# apboard.net
KiCad netlist of a schematic drawn in Altium Designer
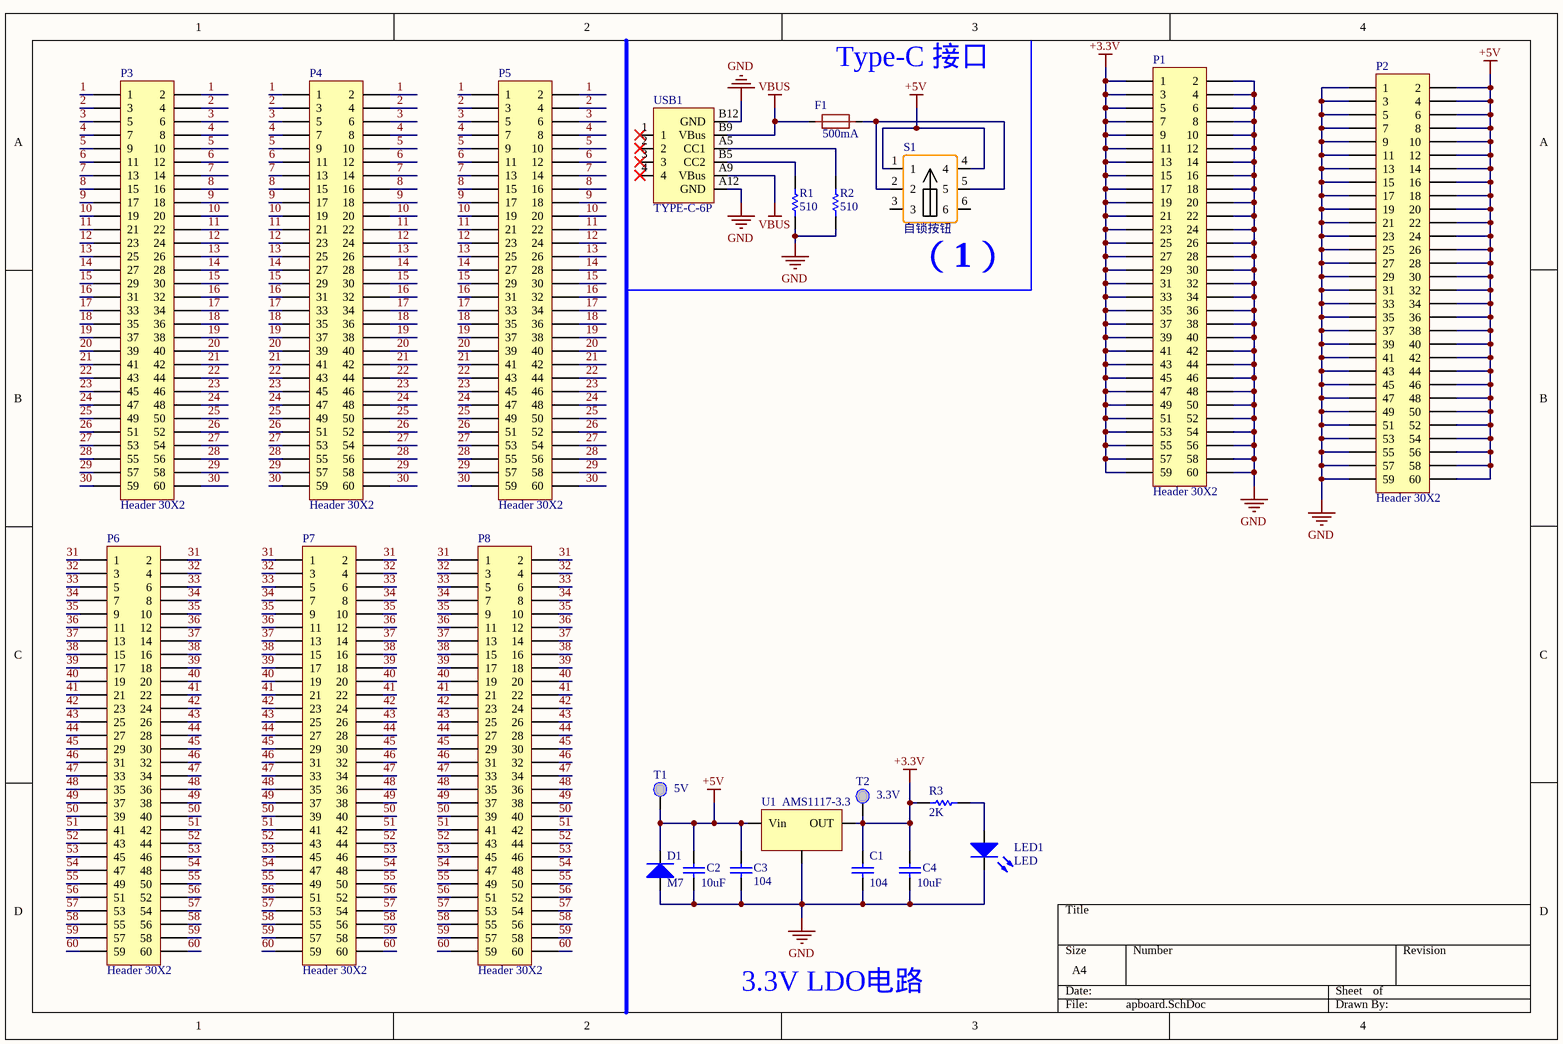
[diagram p0: apboard.SchDoc]

(export (version "E")
  (design (tool "Eeschema 10.0.6"))
  (components
    (comp (ref "C1")
      (value "104")
      (footprint "C0603")
      (description "无极性电容")
      (fields (field (name "Comment") "Cap") (field (name "PUBLISHER") "信念D力量"))
      (libsource (lib "ZSF-90") (part "Cap"))
    )
    (comp (ref "C2")
      (value "10uF")
      (footprint "C1210")
      (description "无极性电容")
      (fields (field (name "Comment") "Cap") (field (name "PUBLISHER") "信念D力量"))
      (libsource (lib "ZSF-90") (part "Cap"))
    )
    (comp (ref "C3")
      (value "104")
      (footprint "C0603")
      (description "无极性电容")
      (fields (field (name "Comment") "Cap") (field (name "PUBLISHER") "信念D力量"))
      (libsource (lib "ZSF-90") (part "Cap"))
    )
    (comp (ref "C4")
      (value "10uF")
      (footprint "C1210")
      (description "无极性电容")
      (fields (field (name "Comment") "Cap") (field (name "PUBLISHER") "信念D力量"))
      (libsource (lib "ZSF-90") (part "Cap"))
    )
    (comp (ref "D1")
      (value "M7")
      (footprint "SOD-123_L2.8-W1.8-LS3.7-RD")
      (description "1N4007 二极管")
      (libsource (lib "ZSF-90") (part "1N4007"))
    )
    (comp (ref "F1")
      (value "500mA")
      (footprint "F0603")
      (description "保险丝 - Fuse")
      (libsource (lib "ZSF-90") (part "Fuse 1"))
    )
    (comp (ref "LED1")
      (value "LED")
      (footprint "LED0603_RED")
      (description "发光二极管")
      (libsource (lib "ZSF-90") (part "LED"))
    )
    (comp (ref "P1")
      (value "Header 30X2")
      (footprint "HDR2X30")
      (description "Header, 30-Pin, Dual row")
      (fields (field (name "PUBLISHER") "Altium Limited"))
      (libsource (lib "ZSF90_Connector") (part "Header 30X2"))
    )
    (comp (ref "P2")
      (value "Header 30X2")
      (footprint "HDR2X30")
      (description "Header, 30-Pin, Dual row")
      (fields (field (name "PUBLISHER") "Altium Limited"))
      (libsource (lib "ZSF90_Connector") (part "Header 30X2"))
    )
    (comp (ref "P3")
      (value "Header 30X2")
      (footprint "HDR2X30")
      (description "Header, 30-Pin, Dual row")
      (fields (field (name "PUBLISHER") "Altium Limited"))
      (libsource (lib "ZSF90_Connector") (part "Header 30X2"))
    )
    (comp (ref "P4")
      (value "Header 30X2")
      (footprint "HDR2X30")
      (description "Header, 30-Pin, Dual row")
      (fields (field (name "PUBLISHER") "Altium Limited"))
      (libsource (lib "ZSF90_Connector") (part "Header 30X2"))
    )
    (comp (ref "P5")
      (value "Header 30X2")
      (footprint "HDR2X30")
      (description "Header, 30-Pin, Dual row")
      (fields (field (name "PUBLISHER") "Altium Limited"))
      (libsource (lib "ZSF90_Connector") (part "Header 30X2"))
    )
    (comp (ref "P6")
      (value "Header 30X2")
      (footprint "HDR2X30")
      (description "Header, 30-Pin, Dual row")
      (fields (field (name "PUBLISHER") "Altium Limited"))
      (libsource (lib "ZSF90_Connector") (part "Header 30X2"))
    )
    (comp (ref "P7")
      (value "Header 30X2")
      (footprint "HDR2X30")
      (description "Header, 30-Pin, Dual row")
      (fields (field (name "PUBLISHER") "Altium Limited"))
      (libsource (lib "ZSF90_Connector") (part "Header 30X2"))
    )
    (comp (ref "P8")
      (value "Header 30X2")
      (footprint "HDR2X30")
      (description "Header, 30-Pin, Dual row")
      (fields (field (name "PUBLISHER") "Altium Limited"))
      (libsource (lib "ZSF90_Connector") (part "Header 30X2"))
    )
    (comp (ref "R1")
      (value "510")
      (footprint "R0603")
      (description "美国电阻符号")
      (fields (field (name "Comment") "Res") (field (name "PUBLISHER") "Altium Limited"))
      (libsource (lib "ZSF-90") (part "Res"))
    )
    (comp (ref "R2")
      (value "510")
      (footprint "R0603")
      (description "美国电阻符号")
      (fields (field (name "Comment") "Res") (field (name "PUBLISHER") "Altium Limited"))
      (libsource (lib "ZSF-90") (part "Res"))
    )
    (comp (ref "R3")
      (value "2K")
      (footprint "R0603")
      (description "美国电阻符号")
      (fields (field (name "Comment") "Res") (field (name "PUBLISHER") "Altium Limited"))
      (libsource (lib "ZSF-90") (part "Res"))
    )
    (comp (ref "S1")
      (value "自锁按钮")
      (footprint "SW-TH_5.8ZSGT")
      (description "自锁按钮开个")
      (libsource (lib "ZSF90_Connector") (part "自锁按钮"))
    )
    (comp (ref "T1") (value "5V") (footprint "TEST-SMD") (libsource (lib "ZSF-90") (part "Test")))
    (comp (ref "T2") (value "3.3V") (footprint "TEST-SMD") (libsource (lib "ZSF-90") (part "Test")))
    (comp (ref "U1")
      (value "AMS1117-3.3")
      (footprint "SOT-223")
      (description "线性稳压芯片 - Voltage Regulator")
      (libsource (lib "ZSF-90") (part "AMS1117-3.3"))
    )
    (comp (ref "USB1")
      (value "TYPE-C-6P")
      (footprint "USB-C-SMD_6P")
      (description "Type-C USB，6P")
      (libsource (lib "ZSF-90") (part "TYPE-C-6P"))
    )
  )
  (nets
    (net (code "1") (name "+3.3V") (class "Default")
      (node (ref "C1") (pin "2") (pinfunction "2_2") (pintype "passive"))
      (node (ref "C4") (pin "2") (pinfunction "2_2") (pintype "passive"))
      (node (ref "P1") (pin "1") (pinfunction "1_1") (pintype "passive"))
      (node (ref "P1") (pin "11") (pinfunction "11_11") (pintype "passive"))
      (node (ref "P1") (pin "13") (pinfunction "13_13") (pintype "passive"))
      (node (ref "P1") (pin "15") (pinfunction "15_15") (pintype "passive"))
      (node (ref "P1") (pin "17") (pinfunction "17_17") (pintype "passive"))
      (node (ref "P1") (pin "19") (pinfunction "19_19") (pintype "passive"))
      (node (ref "P1") (pin "21") (pinfunction "21_21") (pintype "passive"))
      (node (ref "P1") (pin "23") (pinfunction "23_23") (pintype "passive"))
      (node (ref "P1") (pin "25") (pinfunction "25_25") (pintype "passive"))
      (node (ref "P1") (pin "27") (pinfunction "27_27") (pintype "passive"))
      (node (ref "P1") (pin "29") (pinfunction "29_29") (pintype "passive"))
      (node (ref "P1") (pin "3") (pinfunction "3_3") (pintype "passive"))
      (node (ref "P1") (pin "31") (pinfunction "31_31") (pintype "passive"))
      (node (ref "P1") (pin "33") (pinfunction "33_33") (pintype "passive"))
      (node (ref "P1") (pin "35") (pinfunction "35_35") (pintype "passive"))
      (node (ref "P1") (pin "37") (pinfunction "37_37") (pintype "passive"))
      (node (ref "P1") (pin "39") (pinfunction "39_39") (pintype "passive"))
      (node (ref "P1") (pin "41") (pinfunction "41_41") (pintype "passive"))
      (node (ref "P1") (pin "43") (pinfunction "43_43") (pintype "passive"))
      (node (ref "P1") (pin "45") (pinfunction "45_45") (pintype "passive"))
      (node (ref "P1") (pin "47") (pinfunction "47_47") (pintype "passive"))
      (node (ref "P1") (pin "49") (pinfunction "49_49") (pintype "passive"))
      (node (ref "P1") (pin "5") (pinfunction "5_5") (pintype "passive"))
      (node (ref "P1") (pin "51") (pinfunction "51_51") (pintype "passive"))
      (node (ref "P1") (pin "53") (pinfunction "53_53") (pintype "passive"))
      (node (ref "P1") (pin "55") (pinfunction "55_55") (pintype "passive"))
      (node (ref "P1") (pin "57") (pinfunction "57_57") (pintype "passive"))
      (node (ref "P1") (pin "59") (pinfunction "59_59") (pintype "passive"))
      (node (ref "P1") (pin "7") (pinfunction "7_7") (pintype "passive"))
      (node (ref "P1") (pin "9") (pinfunction "9_9") (pintype "passive"))
      (node (ref "R3") (pin "2") (pinfunction "2_2") (pintype "passive"))
      (node (ref "T2") (pin "1") (pinfunction "TEST_1") (pintype "passive"))
      (node (ref "U1") (pin "2") (pinfunction "OUT_2") (pintype "passive"))
    )
    (net (code "2") (name "+5V") (class "Default")
      (node (ref "C2") (pin "2") (pinfunction "2_2") (pintype "passive"))
      (node (ref "C3") (pin "2") (pinfunction "2_2") (pintype "passive"))
      (node (ref "D1") (pin "1") (pinfunction "K_1") (pintype "passive"))
      (node (ref "P2") (pin "10") (pinfunction "10_10") (pintype "passive"))
      (node (ref "P2") (pin "12") (pinfunction "12_12") (pintype "passive"))
      (node (ref "P2") (pin "14") (pinfunction "14_14") (pintype "passive"))
      (node (ref "P2") (pin "16") (pinfunction "16_16") (pintype "passive"))
      (node (ref "P2") (pin "18") (pinfunction "18_18") (pintype "passive"))
      (node (ref "P2") (pin "2") (pinfunction "2_2") (pintype "passive"))
      (node (ref "P2") (pin "20") (pinfunction "20_20") (pintype "passive"))
      (node (ref "P2") (pin "22") (pinfunction "22_22") (pintype "passive"))
      (node (ref "P2") (pin "24") (pinfunction "24_24") (pintype "passive"))
      (node (ref "P2") (pin "26") (pinfunction "26_26") (pintype "passive"))
      (node (ref "P2") (pin "28") (pinfunction "28_28") (pintype "passive"))
      (node (ref "P2") (pin "30") (pinfunction "30_30") (pintype "passive"))
      (node (ref "P2") (pin "32") (pinfunction "32_32") (pintype "passive"))
      (node (ref "P2") (pin "34") (pinfunction "34_34") (pintype "passive"))
      (node (ref "P2") (pin "36") (pinfunction "36_36") (pintype "passive"))
      (node (ref "P2") (pin "38") (pinfunction "38_38") (pintype "passive"))
      (node (ref "P2") (pin "4") (pinfunction "4_4") (pintype "passive"))
      (node (ref "P2") (pin "40") (pinfunction "40_40") (pintype "passive"))
      (node (ref "P2") (pin "42") (pinfunction "42_42") (pintype "passive"))
      (node (ref "P2") (pin "44") (pinfunction "44_44") (pintype "passive"))
      (node (ref "P2") (pin "46") (pinfunction "46_46") (pintype "passive"))
      (node (ref "P2") (pin "48") (pinfunction "48_48") (pintype "passive"))
      (node (ref "P2") (pin "50") (pinfunction "50_50") (pintype "passive"))
      (node (ref "P2") (pin "52") (pinfunction "52_52") (pintype "passive"))
      (node (ref "P2") (pin "54") (pinfunction "54_54") (pintype "passive"))
      (node (ref "P2") (pin "56") (pinfunction "56_56") (pintype "passive"))
      (node (ref "P2") (pin "58") (pinfunction "58_58") (pintype "passive"))
      (node (ref "P2") (pin "6") (pinfunction "6_6") (pintype "passive"))
      (node (ref "P2") (pin "60") (pinfunction "60_60") (pintype "passive"))
      (node (ref "P2") (pin "8") (pinfunction "8_8") (pintype "passive"))
      (node (ref "S1") (pin "1") (pinfunction "1_1") (pintype "passive"))
      (node (ref "S1") (pin "4") (pinfunction "4_4") (pintype "passive"))
      (node (ref "T1") (pin "1") (pinfunction "TEST_1") (pintype "passive"))
      (node (ref "U1") (pin "3") (pinfunction "Vin_3") (pintype "passive"))
    )
    (net (code "3") (name "/1") (class "Default")
      (node (ref "P3") (pin "1") (pinfunction "1_1") (pintype "passive"))
      (node (ref "P3") (pin "2") (pinfunction "2_2") (pintype "passive"))
      (node (ref "P4") (pin "1") (pinfunction "1_1") (pintype "passive"))
      (node (ref "P4") (pin "2") (pinfunction "2_2") (pintype "passive"))
      (node (ref "P5") (pin "1") (pinfunction "1_1") (pintype "passive"))
      (node (ref "P5") (pin "2") (pinfunction "2_2") (pintype "passive"))
    )
    (net (code "4") (name "/2") (class "Default")
      (node (ref "P3") (pin "3") (pinfunction "3_3") (pintype "passive"))
      (node (ref "P3") (pin "4") (pinfunction "4_4") (pintype "passive"))
      (node (ref "P4") (pin "3") (pinfunction "3_3") (pintype "passive"))
      (node (ref "P4") (pin "4") (pinfunction "4_4") (pintype "passive"))
      (node (ref "P5") (pin "3") (pinfunction "3_3") (pintype "passive"))
      (node (ref "P5") (pin "4") (pinfunction "4_4") (pintype "passive"))
    )
    (net (code "5") (name "/3") (class "Default")
      (node (ref "P3") (pin "5") (pinfunction "5_5") (pintype "passive"))
      (node (ref "P3") (pin "6") (pinfunction "6_6") (pintype "passive"))
      (node (ref "P4") (pin "5") (pinfunction "5_5") (pintype "passive"))
      (node (ref "P4") (pin "6") (pinfunction "6_6") (pintype "passive"))
      (node (ref "P5") (pin "5") (pinfunction "5_5") (pintype "passive"))
      (node (ref "P5") (pin "6") (pinfunction "6_6") (pintype "passive"))
    )
    (net (code "6") (name "/4") (class "Default")
      (node (ref "P3") (pin "7") (pinfunction "7_7") (pintype "passive"))
      (node (ref "P3") (pin "8") (pinfunction "8_8") (pintype "passive"))
      (node (ref "P4") (pin "7") (pinfunction "7_7") (pintype "passive"))
      (node (ref "P4") (pin "8") (pinfunction "8_8") (pintype "passive"))
      (node (ref "P5") (pin "7") (pinfunction "7_7") (pintype "passive"))
      (node (ref "P5") (pin "8") (pinfunction "8_8") (pintype "passive"))
    )
    (net (code "7") (name "/5") (class "Default")
      (node (ref "P3") (pin "10") (pinfunction "10_10") (pintype "passive"))
      (node (ref "P3") (pin "9") (pinfunction "9_9") (pintype "passive"))
      (node (ref "P4") (pin "10") (pinfunction "10_10") (pintype "passive"))
      (node (ref "P4") (pin "9") (pinfunction "9_9") (pintype "passive"))
      (node (ref "P5") (pin "10") (pinfunction "10_10") (pintype "passive"))
      (node (ref "P5") (pin "9") (pinfunction "9_9") (pintype "passive"))
    )
    (net (code "8") (name "/6") (class "Default")
      (node (ref "P3") (pin "11") (pinfunction "11_11") (pintype "passive"))
      (node (ref "P3") (pin "12") (pinfunction "12_12") (pintype "passive"))
      (node (ref "P4") (pin "11") (pinfunction "11_11") (pintype "passive"))
      (node (ref "P4") (pin "12") (pinfunction "12_12") (pintype "passive"))
      (node (ref "P5") (pin "11") (pinfunction "11_11") (pintype "passive"))
      (node (ref "P5") (pin "12") (pinfunction "12_12") (pintype "passive"))
    )
    (net (code "9") (name "/7") (class "Default")
      (node (ref "P3") (pin "13") (pinfunction "13_13") (pintype "passive"))
      (node (ref "P3") (pin "14") (pinfunction "14_14") (pintype "passive"))
      (node (ref "P4") (pin "13") (pinfunction "13_13") (pintype "passive"))
      (node (ref "P4") (pin "14") (pinfunction "14_14") (pintype "passive"))
      (node (ref "P5") (pin "13") (pinfunction "13_13") (pintype "passive"))
      (node (ref "P5") (pin "14") (pinfunction "14_14") (pintype "passive"))
    )
    (net (code "10") (name "/8") (class "Default")
      (node (ref "P3") (pin "15") (pinfunction "15_15") (pintype "passive"))
      (node (ref "P3") (pin "16") (pinfunction "16_16") (pintype "passive"))
      (node (ref "P4") (pin "15") (pinfunction "15_15") (pintype "passive"))
      (node (ref "P4") (pin "16") (pinfunction "16_16") (pintype "passive"))
      (node (ref "P5") (pin "15") (pinfunction "15_15") (pintype "passive"))
      (node (ref "P5") (pin "16") (pinfunction "16_16") (pintype "passive"))
    )
    (net (code "11") (name "/9") (class "Default")
      (node (ref "P3") (pin "17") (pinfunction "17_17") (pintype "passive"))
      (node (ref "P3") (pin "18") (pinfunction "18_18") (pintype "passive"))
      (node (ref "P4") (pin "17") (pinfunction "17_17") (pintype "passive"))
      (node (ref "P4") (pin "18") (pinfunction "18_18") (pintype "passive"))
      (node (ref "P5") (pin "17") (pinfunction "17_17") (pintype "passive"))
      (node (ref "P5") (pin "18") (pinfunction "18_18") (pintype "passive"))
    )
    (net (code "12") (name "/10") (class "Default")
      (node (ref "P3") (pin "19") (pinfunction "19_19") (pintype "passive"))
      (node (ref "P3") (pin "20") (pinfunction "20_20") (pintype "passive"))
      (node (ref "P4") (pin "19") (pinfunction "19_19") (pintype "passive"))
      (node (ref "P4") (pin "20") (pinfunction "20_20") (pintype "passive"))
      (node (ref "P5") (pin "19") (pinfunction "19_19") (pintype "passive"))
      (node (ref "P5") (pin "20") (pinfunction "20_20") (pintype "passive"))
    )
    (net (code "13") (name "/11") (class "Default")
      (node (ref "P3") (pin "21") (pinfunction "21_21") (pintype "passive"))
      (node (ref "P3") (pin "22") (pinfunction "22_22") (pintype "passive"))
      (node (ref "P4") (pin "21") (pinfunction "21_21") (pintype "passive"))
      (node (ref "P4") (pin "22") (pinfunction "22_22") (pintype "passive"))
      (node (ref "P5") (pin "21") (pinfunction "21_21") (pintype "passive"))
      (node (ref "P5") (pin "22") (pinfunction "22_22") (pintype "passive"))
    )
    (net (code "14") (name "/12") (class "Default")
      (node (ref "P3") (pin "23") (pinfunction "23_23") (pintype "passive"))
      (node (ref "P3") (pin "24") (pinfunction "24_24") (pintype "passive"))
      (node (ref "P4") (pin "23") (pinfunction "23_23") (pintype "passive"))
      (node (ref "P4") (pin "24") (pinfunction "24_24") (pintype "passive"))
      (node (ref "P5") (pin "23") (pinfunction "23_23") (pintype "passive"))
      (node (ref "P5") (pin "24") (pinfunction "24_24") (pintype "passive"))
    )
    (net (code "15") (name "/13") (class "Default")
      (node (ref "P3") (pin "25") (pinfunction "25_25") (pintype "passive"))
      (node (ref "P3") (pin "26") (pinfunction "26_26") (pintype "passive"))
      (node (ref "P4") (pin "25") (pinfunction "25_25") (pintype "passive"))
      (node (ref "P4") (pin "26") (pinfunction "26_26") (pintype "passive"))
      (node (ref "P5") (pin "25") (pinfunction "25_25") (pintype "passive"))
      (node (ref "P5") (pin "26") (pinfunction "26_26") (pintype "passive"))
    )
    (net (code "16") (name "/14") (class "Default")
      (node (ref "P3") (pin "27") (pinfunction "27_27") (pintype "passive"))
      (node (ref "P3") (pin "28") (pinfunction "28_28") (pintype "passive"))
      (node (ref "P4") (pin "27") (pinfunction "27_27") (pintype "passive"))
      (node (ref "P4") (pin "28") (pinfunction "28_28") (pintype "passive"))
      (node (ref "P5") (pin "27") (pinfunction "27_27") (pintype "passive"))
      (node (ref "P5") (pin "28") (pinfunction "28_28") (pintype "passive"))
    )
    (net (code "17") (name "/15") (class "Default")
      (node (ref "P3") (pin "29") (pinfunction "29_29") (pintype "passive"))
      (node (ref "P3") (pin "30") (pinfunction "30_30") (pintype "passive"))
      (node (ref "P4") (pin "29") (pinfunction "29_29") (pintype "passive"))
      (node (ref "P4") (pin "30") (pinfunction "30_30") (pintype "passive"))
      (node (ref "P5") (pin "29") (pinfunction "29_29") (pintype "passive"))
      (node (ref "P5") (pin "30") (pinfunction "30_30") (pintype "passive"))
    )
    (net (code "18") (name "/16") (class "Default")
      (node (ref "P3") (pin "31") (pinfunction "31_31") (pintype "passive"))
      (node (ref "P3") (pin "32") (pinfunction "32_32") (pintype "passive"))
      (node (ref "P4") (pin "31") (pinfunction "31_31") (pintype "passive"))
      (node (ref "P4") (pin "32") (pinfunction "32_32") (pintype "passive"))
      (node (ref "P5") (pin "31") (pinfunction "31_31") (pintype "passive"))
      (node (ref "P5") (pin "32") (pinfunction "32_32") (pintype "passive"))
    )
    (net (code "19") (name "/17") (class "Default")
      (node (ref "P3") (pin "33") (pinfunction "33_33") (pintype "passive"))
      (node (ref "P3") (pin "34") (pinfunction "34_34") (pintype "passive"))
      (node (ref "P4") (pin "33") (pinfunction "33_33") (pintype "passive"))
      (node (ref "P4") (pin "34") (pinfunction "34_34") (pintype "passive"))
      (node (ref "P5") (pin "33") (pinfunction "33_33") (pintype "passive"))
      (node (ref "P5") (pin "34") (pinfunction "34_34") (pintype "passive"))
    )
    (net (code "20") (name "/18") (class "Default")
      (node (ref "P3") (pin "35") (pinfunction "35_35") (pintype "passive"))
      (node (ref "P3") (pin "36") (pinfunction "36_36") (pintype "passive"))
      (node (ref "P4") (pin "35") (pinfunction "35_35") (pintype "passive"))
      (node (ref "P4") (pin "36") (pinfunction "36_36") (pintype "passive"))
      (node (ref "P5") (pin "35") (pinfunction "35_35") (pintype "passive"))
      (node (ref "P5") (pin "36") (pinfunction "36_36") (pintype "passive"))
    )
    (net (code "21") (name "/19") (class "Default")
      (node (ref "P3") (pin "37") (pinfunction "37_37") (pintype "passive"))
      (node (ref "P3") (pin "38") (pinfunction "38_38") (pintype "passive"))
      (node (ref "P4") (pin "37") (pinfunction "37_37") (pintype "passive"))
      (node (ref "P4") (pin "38") (pinfunction "38_38") (pintype "passive"))
      (node (ref "P5") (pin "37") (pinfunction "37_37") (pintype "passive"))
      (node (ref "P5") (pin "38") (pinfunction "38_38") (pintype "passive"))
    )
    (net (code "22") (name "/20") (class "Default")
      (node (ref "P3") (pin "39") (pinfunction "39_39") (pintype "passive"))
      (node (ref "P3") (pin "40") (pinfunction "40_40") (pintype "passive"))
      (node (ref "P4") (pin "39") (pinfunction "39_39") (pintype "passive"))
      (node (ref "P4") (pin "40") (pinfunction "40_40") (pintype "passive"))
      (node (ref "P5") (pin "39") (pinfunction "39_39") (pintype "passive"))
      (node (ref "P5") (pin "40") (pinfunction "40_40") (pintype "passive"))
    )
    (net (code "23") (name "/21") (class "Default")
      (node (ref "P3") (pin "41") (pinfunction "41_41") (pintype "passive"))
      (node (ref "P3") (pin "42") (pinfunction "42_42") (pintype "passive"))
      (node (ref "P4") (pin "41") (pinfunction "41_41") (pintype "passive"))
      (node (ref "P4") (pin "42") (pinfunction "42_42") (pintype "passive"))
      (node (ref "P5") (pin "41") (pinfunction "41_41") (pintype "passive"))
      (node (ref "P5") (pin "42") (pinfunction "42_42") (pintype "passive"))
    )
    (net (code "24") (name "/22") (class "Default")
      (node (ref "P3") (pin "43") (pinfunction "43_43") (pintype "passive"))
      (node (ref "P3") (pin "44") (pinfunction "44_44") (pintype "passive"))
      (node (ref "P4") (pin "43") (pinfunction "43_43") (pintype "passive"))
      (node (ref "P4") (pin "44") (pinfunction "44_44") (pintype "passive"))
      (node (ref "P5") (pin "43") (pinfunction "43_43") (pintype "passive"))
      (node (ref "P5") (pin "44") (pinfunction "44_44") (pintype "passive"))
    )
    (net (code "25") (name "/23") (class "Default")
      (node (ref "P3") (pin "45") (pinfunction "45_45") (pintype "passive"))
      (node (ref "P3") (pin "46") (pinfunction "46_46") (pintype "passive"))
      (node (ref "P4") (pin "45") (pinfunction "45_45") (pintype "passive"))
      (node (ref "P4") (pin "46") (pinfunction "46_46") (pintype "passive"))
      (node (ref "P5") (pin "45") (pinfunction "45_45") (pintype "passive"))
      (node (ref "P5") (pin "46") (pinfunction "46_46") (pintype "passive"))
    )
    (net (code "26") (name "/24") (class "Default")
      (node (ref "P3") (pin "47") (pinfunction "47_47") (pintype "passive"))
      (node (ref "P3") (pin "48") (pinfunction "48_48") (pintype "passive"))
      (node (ref "P4") (pin "47") (pinfunction "47_47") (pintype "passive"))
      (node (ref "P4") (pin "48") (pinfunction "48_48") (pintype "passive"))
      (node (ref "P5") (pin "47") (pinfunction "47_47") (pintype "passive"))
      (node (ref "P5") (pin "48") (pinfunction "48_48") (pintype "passive"))
    )
    (net (code "27") (name "/25") (class "Default")
      (node (ref "P3") (pin "49") (pinfunction "49_49") (pintype "passive"))
      (node (ref "P3") (pin "50") (pinfunction "50_50") (pintype "passive"))
      (node (ref "P4") (pin "49") (pinfunction "49_49") (pintype "passive"))
      (node (ref "P4") (pin "50") (pinfunction "50_50") (pintype "passive"))
      (node (ref "P5") (pin "49") (pinfunction "49_49") (pintype "passive"))
      (node (ref "P5") (pin "50") (pinfunction "50_50") (pintype "passive"))
    )
    (net (code "28") (name "/26") (class "Default")
      (node (ref "P3") (pin "51") (pinfunction "51_51") (pintype "passive"))
      (node (ref "P3") (pin "52") (pinfunction "52_52") (pintype "passive"))
      (node (ref "P4") (pin "51") (pinfunction "51_51") (pintype "passive"))
      (node (ref "P4") (pin "52") (pinfunction "52_52") (pintype "passive"))
      (node (ref "P5") (pin "51") (pinfunction "51_51") (pintype "passive"))
      (node (ref "P5") (pin "52") (pinfunction "52_52") (pintype "passive"))
    )
    (net (code "29") (name "/27") (class "Default")
      (node (ref "P3") (pin "53") (pinfunction "53_53") (pintype "passive"))
      (node (ref "P3") (pin "54") (pinfunction "54_54") (pintype "passive"))
      (node (ref "P4") (pin "53") (pinfunction "53_53") (pintype "passive"))
      (node (ref "P4") (pin "54") (pinfunction "54_54") (pintype "passive"))
      (node (ref "P5") (pin "53") (pinfunction "53_53") (pintype "passive"))
      (node (ref "P5") (pin "54") (pinfunction "54_54") (pintype "passive"))
    )
    (net (code "30") (name "/28") (class "Default")
      (node (ref "P3") (pin "55") (pinfunction "55_55") (pintype "passive"))
      (node (ref "P3") (pin "56") (pinfunction "56_56") (pintype "passive"))
      (node (ref "P4") (pin "55") (pinfunction "55_55") (pintype "passive"))
      (node (ref "P4") (pin "56") (pinfunction "56_56") (pintype "passive"))
      (node (ref "P5") (pin "55") (pinfunction "55_55") (pintype "passive"))
      (node (ref "P5") (pin "56") (pinfunction "56_56") (pintype "passive"))
    )
    (net (code "31") (name "/29") (class "Default")
      (node (ref "P3") (pin "57") (pinfunction "57_57") (pintype "passive"))
      (node (ref "P3") (pin "58") (pinfunction "58_58") (pintype "passive"))
      (node (ref "P4") (pin "57") (pinfunction "57_57") (pintype "passive"))
      (node (ref "P4") (pin "58") (pinfunction "58_58") (pintype "passive"))
      (node (ref "P5") (pin "57") (pinfunction "57_57") (pintype "passive"))
      (node (ref "P5") (pin "58") (pinfunction "58_58") (pintype "passive"))
    )
    (net (code "32") (name "/30") (class "Default")
      (node (ref "P3") (pin "59") (pinfunction "59_59") (pintype "passive"))
      (node (ref "P3") (pin "60") (pinfunction "60_60") (pintype "passive"))
      (node (ref "P4") (pin "59") (pinfunction "59_59") (pintype "passive"))
      (node (ref "P4") (pin "60") (pinfunction "60_60") (pintype "passive"))
      (node (ref "P5") (pin "59") (pinfunction "59_59") (pintype "passive"))
      (node (ref "P5") (pin "60") (pinfunction "60_60") (pintype "passive"))
    )
    (net (code "33") (name "/31") (class "Default")
      (node (ref "P6") (pin "1") (pinfunction "1_1") (pintype "passive"))
      (node (ref "P6") (pin "2") (pinfunction "2_2") (pintype "passive"))
      (node (ref "P7") (pin "1") (pinfunction "1_1") (pintype "passive"))
      (node (ref "P7") (pin "2") (pinfunction "2_2") (pintype "passive"))
      (node (ref "P8") (pin "1") (pinfunction "1_1") (pintype "passive"))
      (node (ref "P8") (pin "2") (pinfunction "2_2") (pintype "passive"))
    )
    (net (code "34") (name "/32") (class "Default")
      (node (ref "P6") (pin "3") (pinfunction "3_3") (pintype "passive"))
      (node (ref "P6") (pin "4") (pinfunction "4_4") (pintype "passive"))
      (node (ref "P7") (pin "3") (pinfunction "3_3") (pintype "passive"))
      (node (ref "P7") (pin "4") (pinfunction "4_4") (pintype "passive"))
      (node (ref "P8") (pin "3") (pinfunction "3_3") (pintype "passive"))
      (node (ref "P8") (pin "4") (pinfunction "4_4") (pintype "passive"))
    )
    (net (code "35") (name "/33") (class "Default")
      (node (ref "P6") (pin "5") (pinfunction "5_5") (pintype "passive"))
      (node (ref "P6") (pin "6") (pinfunction "6_6") (pintype "passive"))
      (node (ref "P7") (pin "5") (pinfunction "5_5") (pintype "passive"))
      (node (ref "P7") (pin "6") (pinfunction "6_6") (pintype "passive"))
      (node (ref "P8") (pin "5") (pinfunction "5_5") (pintype "passive"))
      (node (ref "P8") (pin "6") (pinfunction "6_6") (pintype "passive"))
    )
    (net (code "36") (name "/34") (class "Default")
      (node (ref "P6") (pin "7") (pinfunction "7_7") (pintype "passive"))
      (node (ref "P6") (pin "8") (pinfunction "8_8") (pintype "passive"))
      (node (ref "P7") (pin "7") (pinfunction "7_7") (pintype "passive"))
      (node (ref "P7") (pin "8") (pinfunction "8_8") (pintype "passive"))
      (node (ref "P8") (pin "7") (pinfunction "7_7") (pintype "passive"))
      (node (ref "P8") (pin "8") (pinfunction "8_8") (pintype "passive"))
    )
    (net (code "37") (name "/35") (class "Default")
      (node (ref "P6") (pin "10") (pinfunction "10_10") (pintype "passive"))
      (node (ref "P6") (pin "9") (pinfunction "9_9") (pintype "passive"))
      (node (ref "P7") (pin "10") (pinfunction "10_10") (pintype "passive"))
      (node (ref "P7") (pin "9") (pinfunction "9_9") (pintype "passive"))
      (node (ref "P8") (pin "10") (pinfunction "10_10") (pintype "passive"))
      (node (ref "P8") (pin "9") (pinfunction "9_9") (pintype "passive"))
    )
    (net (code "38") (name "/36") (class "Default")
      (node (ref "P6") (pin "11") (pinfunction "11_11") (pintype "passive"))
      (node (ref "P6") (pin "12") (pinfunction "12_12") (pintype "passive"))
      (node (ref "P7") (pin "11") (pinfunction "11_11") (pintype "passive"))
      (node (ref "P7") (pin "12") (pinfunction "12_12") (pintype "passive"))
      (node (ref "P8") (pin "11") (pinfunction "11_11") (pintype "passive"))
      (node (ref "P8") (pin "12") (pinfunction "12_12") (pintype "passive"))
    )
    (net (code "39") (name "/37") (class "Default")
      (node (ref "P6") (pin "13") (pinfunction "13_13") (pintype "passive"))
      (node (ref "P6") (pin "14") (pinfunction "14_14") (pintype "passive"))
      (node (ref "P7") (pin "13") (pinfunction "13_13") (pintype "passive"))
      (node (ref "P7") (pin "14") (pinfunction "14_14") (pintype "passive"))
      (node (ref "P8") (pin "13") (pinfunction "13_13") (pintype "passive"))
      (node (ref "P8") (pin "14") (pinfunction "14_14") (pintype "passive"))
    )
    (net (code "40") (name "/38") (class "Default")
      (node (ref "P6") (pin "15") (pinfunction "15_15") (pintype "passive"))
      (node (ref "P6") (pin "16") (pinfunction "16_16") (pintype "passive"))
      (node (ref "P7") (pin "15") (pinfunction "15_15") (pintype "passive"))
      (node (ref "P7") (pin "16") (pinfunction "16_16") (pintype "passive"))
      (node (ref "P8") (pin "15") (pinfunction "15_15") (pintype "passive"))
      (node (ref "P8") (pin "16") (pinfunction "16_16") (pintype "passive"))
    )
    (net (code "41") (name "/39") (class "Default")
      (node (ref "P6") (pin "17") (pinfunction "17_17") (pintype "passive"))
      (node (ref "P6") (pin "18") (pinfunction "18_18") (pintype "passive"))
      (node (ref "P7") (pin "17") (pinfunction "17_17") (pintype "passive"))
      (node (ref "P7") (pin "18") (pinfunction "18_18") (pintype "passive"))
      (node (ref "P8") (pin "17") (pinfunction "17_17") (pintype "passive"))
      (node (ref "P8") (pin "18") (pinfunction "18_18") (pintype "passive"))
    )
    (net (code "42") (name "/40") (class "Default")
      (node (ref "P6") (pin "19") (pinfunction "19_19") (pintype "passive"))
      (node (ref "P6") (pin "20") (pinfunction "20_20") (pintype "passive"))
      (node (ref "P7") (pin "19") (pinfunction "19_19") (pintype "passive"))
      (node (ref "P7") (pin "20") (pinfunction "20_20") (pintype "passive"))
      (node (ref "P8") (pin "19") (pinfunction "19_19") (pintype "passive"))
      (node (ref "P8") (pin "20") (pinfunction "20_20") (pintype "passive"))
    )
    (net (code "43") (name "/41") (class "Default")
      (node (ref "P6") (pin "21") (pinfunction "21_21") (pintype "passive"))
      (node (ref "P6") (pin "22") (pinfunction "22_22") (pintype "passive"))
      (node (ref "P7") (pin "21") (pinfunction "21_21") (pintype "passive"))
      (node (ref "P7") (pin "22") (pinfunction "22_22") (pintype "passive"))
      (node (ref "P8") (pin "21") (pinfunction "21_21") (pintype "passive"))
      (node (ref "P8") (pin "22") (pinfunction "22_22") (pintype "passive"))
    )
    (net (code "44") (name "/42") (class "Default")
      (node (ref "P6") (pin "23") (pinfunction "23_23") (pintype "passive"))
      (node (ref "P6") (pin "24") (pinfunction "24_24") (pintype "passive"))
      (node (ref "P7") (pin "23") (pinfunction "23_23") (pintype "passive"))
      (node (ref "P7") (pin "24") (pinfunction "24_24") (pintype "passive"))
      (node (ref "P8") (pin "23") (pinfunction "23_23") (pintype "passive"))
      (node (ref "P8") (pin "24") (pinfunction "24_24") (pintype "passive"))
    )
    (net (code "45") (name "/43") (class "Default")
      (node (ref "P6") (pin "25") (pinfunction "25_25") (pintype "passive"))
      (node (ref "P6") (pin "26") (pinfunction "26_26") (pintype "passive"))
      (node (ref "P7") (pin "25") (pinfunction "25_25") (pintype "passive"))
      (node (ref "P7") (pin "26") (pinfunction "26_26") (pintype "passive"))
      (node (ref "P8") (pin "25") (pinfunction "25_25") (pintype "passive"))
      (node (ref "P8") (pin "26") (pinfunction "26_26") (pintype "passive"))
    )
    (net (code "46") (name "/44") (class "Default")
      (node (ref "P6") (pin "27") (pinfunction "27_27") (pintype "passive"))
      (node (ref "P6") (pin "28") (pinfunction "28_28") (pintype "passive"))
      (node (ref "P7") (pin "27") (pinfunction "27_27") (pintype "passive"))
      (node (ref "P7") (pin "28") (pinfunction "28_28") (pintype "passive"))
      (node (ref "P8") (pin "27") (pinfunction "27_27") (pintype "passive"))
      (node (ref "P8") (pin "28") (pinfunction "28_28") (pintype "passive"))
    )
    (net (code "47") (name "/45") (class "Default")
      (node (ref "P6") (pin "29") (pinfunction "29_29") (pintype "passive"))
      (node (ref "P6") (pin "30") (pinfunction "30_30") (pintype "passive"))
      (node (ref "P7") (pin "29") (pinfunction "29_29") (pintype "passive"))
      (node (ref "P7") (pin "30") (pinfunction "30_30") (pintype "passive"))
      (node (ref "P8") (pin "29") (pinfunction "29_29") (pintype "passive"))
      (node (ref "P8") (pin "30") (pinfunction "30_30") (pintype "passive"))
    )
    (net (code "48") (name "/46") (class "Default")
      (node (ref "P6") (pin "31") (pinfunction "31_31") (pintype "passive"))
      (node (ref "P6") (pin "32") (pinfunction "32_32") (pintype "passive"))
      (node (ref "P7") (pin "31") (pinfunction "31_31") (pintype "passive"))
      (node (ref "P7") (pin "32") (pinfunction "32_32") (pintype "passive"))
      (node (ref "P8") (pin "31") (pinfunction "31_31") (pintype "passive"))
      (node (ref "P8") (pin "32") (pinfunction "32_32") (pintype "passive"))
    )
    (net (code "49") (name "/47") (class "Default")
      (node (ref "P6") (pin "33") (pinfunction "33_33") (pintype "passive"))
      (node (ref "P6") (pin "34") (pinfunction "34_34") (pintype "passive"))
      (node (ref "P7") (pin "33") (pinfunction "33_33") (pintype "passive"))
      (node (ref "P7") (pin "34") (pinfunction "34_34") (pintype "passive"))
      (node (ref "P8") (pin "33") (pinfunction "33_33") (pintype "passive"))
      (node (ref "P8") (pin "34") (pinfunction "34_34") (pintype "passive"))
    )
    (net (code "50") (name "/48") (class "Default")
      (node (ref "P6") (pin "35") (pinfunction "35_35") (pintype "passive"))
      (node (ref "P6") (pin "36") (pinfunction "36_36") (pintype "passive"))
      (node (ref "P7") (pin "35") (pinfunction "35_35") (pintype "passive"))
      (node (ref "P7") (pin "36") (pinfunction "36_36") (pintype "passive"))
      (node (ref "P8") (pin "35") (pinfunction "35_35") (pintype "passive"))
      (node (ref "P8") (pin "36") (pinfunction "36_36") (pintype "passive"))
    )
    (net (code "51") (name "/49") (class "Default")
      (node (ref "P6") (pin "37") (pinfunction "37_37") (pintype "passive"))
      (node (ref "P6") (pin "38") (pinfunction "38_38") (pintype "passive"))
      (node (ref "P7") (pin "37") (pinfunction "37_37") (pintype "passive"))
      (node (ref "P7") (pin "38") (pinfunction "38_38") (pintype "passive"))
      (node (ref "P8") (pin "37") (pinfunction "37_37") (pintype "passive"))
      (node (ref "P8") (pin "38") (pinfunction "38_38") (pintype "passive"))
    )
    (net (code "52") (name "/50") (class "Default")
      (node (ref "P6") (pin "39") (pinfunction "39_39") (pintype "passive"))
      (node (ref "P6") (pin "40") (pinfunction "40_40") (pintype "passive"))
      (node (ref "P7") (pin "39") (pinfunction "39_39") (pintype "passive"))
      (node (ref "P7") (pin "40") (pinfunction "40_40") (pintype "passive"))
      (node (ref "P8") (pin "39") (pinfunction "39_39") (pintype "passive"))
      (node (ref "P8") (pin "40") (pinfunction "40_40") (pintype "passive"))
    )
    (net (code "53") (name "/51") (class "Default")
      (node (ref "P6") (pin "41") (pinfunction "41_41") (pintype "passive"))
      (node (ref "P6") (pin "42") (pinfunction "42_42") (pintype "passive"))
      (node (ref "P7") (pin "41") (pinfunction "41_41") (pintype "passive"))
      (node (ref "P7") (pin "42") (pinfunction "42_42") (pintype "passive"))
      (node (ref "P8") (pin "41") (pinfunction "41_41") (pintype "passive"))
      (node (ref "P8") (pin "42") (pinfunction "42_42") (pintype "passive"))
    )
    (net (code "54") (name "/52") (class "Default")
      (node (ref "P6") (pin "43") (pinfunction "43_43") (pintype "passive"))
      (node (ref "P6") (pin "44") (pinfunction "44_44") (pintype "passive"))
      (node (ref "P7") (pin "43") (pinfunction "43_43") (pintype "passive"))
      (node (ref "P7") (pin "44") (pinfunction "44_44") (pintype "passive"))
      (node (ref "P8") (pin "43") (pinfunction "43_43") (pintype "passive"))
      (node (ref "P8") (pin "44") (pinfunction "44_44") (pintype "passive"))
    )
    (net (code "55") (name "/53") (class "Default")
      (node (ref "P6") (pin "45") (pinfunction "45_45") (pintype "passive"))
      (node (ref "P6") (pin "46") (pinfunction "46_46") (pintype "passive"))
      (node (ref "P7") (pin "45") (pinfunction "45_45") (pintype "passive"))
      (node (ref "P7") (pin "46") (pinfunction "46_46") (pintype "passive"))
      (node (ref "P8") (pin "45") (pinfunction "45_45") (pintype "passive"))
      (node (ref "P8") (pin "46") (pinfunction "46_46") (pintype "passive"))
    )
    (net (code "56") (name "/54") (class "Default")
      (node (ref "P6") (pin "47") (pinfunction "47_47") (pintype "passive"))
      (node (ref "P6") (pin "48") (pinfunction "48_48") (pintype "passive"))
      (node (ref "P7") (pin "47") (pinfunction "47_47") (pintype "passive"))
      (node (ref "P7") (pin "48") (pinfunction "48_48") (pintype "passive"))
      (node (ref "P8") (pin "47") (pinfunction "47_47") (pintype "passive"))
      (node (ref "P8") (pin "48") (pinfunction "48_48") (pintype "passive"))
    )
    (net (code "57") (name "/55") (class "Default")
      (node (ref "P6") (pin "49") (pinfunction "49_49") (pintype "passive"))
      (node (ref "P6") (pin "50") (pinfunction "50_50") (pintype "passive"))
      (node (ref "P7") (pin "49") (pinfunction "49_49") (pintype "passive"))
      (node (ref "P7") (pin "50") (pinfunction "50_50") (pintype "passive"))
      (node (ref "P8") (pin "49") (pinfunction "49_49") (pintype "passive"))
      (node (ref "P8") (pin "50") (pinfunction "50_50") (pintype "passive"))
    )
    (net (code "58") (name "/56") (class "Default")
      (node (ref "P6") (pin "51") (pinfunction "51_51") (pintype "passive"))
      (node (ref "P6") (pin "52") (pinfunction "52_52") (pintype "passive"))
      (node (ref "P7") (pin "51") (pinfunction "51_51") (pintype "passive"))
      (node (ref "P7") (pin "52") (pinfunction "52_52") (pintype "passive"))
      (node (ref "P8") (pin "51") (pinfunction "51_51") (pintype "passive"))
      (node (ref "P8") (pin "52") (pinfunction "52_52") (pintype "passive"))
    )
    (net (code "59") (name "/57") (class "Default")
      (node (ref "P6") (pin "53") (pinfunction "53_53") (pintype "passive"))
      (node (ref "P6") (pin "54") (pinfunction "54_54") (pintype "passive"))
      (node (ref "P7") (pin "53") (pinfunction "53_53") (pintype "passive"))
      (node (ref "P7") (pin "54") (pinfunction "54_54") (pintype "passive"))
      (node (ref "P8") (pin "53") (pinfunction "53_53") (pintype "passive"))
      (node (ref "P8") (pin "54") (pinfunction "54_54") (pintype "passive"))
    )
    (net (code "60") (name "/58") (class "Default")
      (node (ref "P6") (pin "55") (pinfunction "55_55") (pintype "passive"))
      (node (ref "P6") (pin "56") (pinfunction "56_56") (pintype "passive"))
      (node (ref "P7") (pin "55") (pinfunction "55_55") (pintype "passive"))
      (node (ref "P7") (pin "56") (pinfunction "56_56") (pintype "passive"))
      (node (ref "P8") (pin "55") (pinfunction "55_55") (pintype "passive"))
      (node (ref "P8") (pin "56") (pinfunction "56_56") (pintype "passive"))
    )
    (net (code "61") (name "/59") (class "Default")
      (node (ref "P6") (pin "57") (pinfunction "57_57") (pintype "passive"))
      (node (ref "P6") (pin "58") (pinfunction "58_58") (pintype "passive"))
      (node (ref "P7") (pin "57") (pinfunction "57_57") (pintype "passive"))
      (node (ref "P7") (pin "58") (pinfunction "58_58") (pintype "passive"))
      (node (ref "P8") (pin "57") (pinfunction "57_57") (pintype "passive"))
      (node (ref "P8") (pin "58") (pinfunction "58_58") (pintype "passive"))
    )
    (net (code "62") (name "/60") (class "Default")
      (node (ref "P6") (pin "59") (pinfunction "59_59") (pintype "passive"))
      (node (ref "P6") (pin "60") (pinfunction "60_60") (pintype "passive"))
      (node (ref "P7") (pin "59") (pinfunction "59_59") (pintype "passive"))
      (node (ref "P7") (pin "60") (pinfunction "60_60") (pintype "passive"))
      (node (ref "P8") (pin "59") (pinfunction "59_59") (pintype "passive"))
      (node (ref "P8") (pin "60") (pinfunction "60_60") (pintype "passive"))
    )
    (net (code "63") (name "GND") (class "Default")
      (node (ref "C1") (pin "1") (pinfunction "1_1") (pintype "passive"))
      (node (ref "C2") (pin "1") (pinfunction "1_1") (pintype "passive"))
      (node (ref "C3") (pin "1") (pinfunction "1_1") (pintype "passive"))
      (node (ref "C4") (pin "1") (pinfunction "1_1") (pintype "passive"))
      (node (ref "D1") (pin "2") (pinfunction "A_2") (pintype "passive"))
      (node (ref "LED1") (pin "2") (pinfunction "K_2") (pintype "passive"))
      (node (ref "P1") (pin "10") (pinfunction "10_10") (pintype "passive"))
      (node (ref "P1") (pin "12") (pinfunction "12_12") (pintype "passive"))
      (node (ref "P1") (pin "14") (pinfunction "14_14") (pintype "passive"))
      (node (ref "P1") (pin "16") (pinfunction "16_16") (pintype "passive"))
      (node (ref "P1") (pin "18") (pinfunction "18_18") (pintype "passive"))
      (node (ref "P1") (pin "2") (pinfunction "2_2") (pintype "passive"))
      (node (ref "P1") (pin "20") (pinfunction "20_20") (pintype "passive"))
      (node (ref "P1") (pin "22") (pinfunction "22_22") (pintype "passive"))
      (node (ref "P1") (pin "24") (pinfunction "24_24") (pintype "passive"))
      (node (ref "P1") (pin "26") (pinfunction "26_26") (pintype "passive"))
      (node (ref "P1") (pin "28") (pinfunction "28_28") (pintype "passive"))
      (node (ref "P1") (pin "30") (pinfunction "30_30") (pintype "passive"))
      (node (ref "P1") (pin "32") (pinfunction "32_32") (pintype "passive"))
      (node (ref "P1") (pin "34") (pinfunction "34_34") (pintype "passive"))
      (node (ref "P1") (pin "36") (pinfunction "36_36") (pintype "passive"))
      (node (ref "P1") (pin "38") (pinfunction "38_38") (pintype "passive"))
      (node (ref "P1") (pin "4") (pinfunction "4_4") (pintype "passive"))
      (node (ref "P1") (pin "40") (pinfunction "40_40") (pintype "passive"))
      (node (ref "P1") (pin "42") (pinfunction "42_42") (pintype "passive"))
      (node (ref "P1") (pin "44") (pinfunction "44_44") (pintype "passive"))
      (node (ref "P1") (pin "46") (pinfunction "46_46") (pintype "passive"))
      (node (ref "P1") (pin "48") (pinfunction "48_48") (pintype "passive"))
      (node (ref "P1") (pin "50") (pinfunction "50_50") (pintype "passive"))
      (node (ref "P1") (pin "52") (pinfunction "52_52") (pintype "passive"))
      (node (ref "P1") (pin "54") (pinfunction "54_54") (pintype "passive"))
      (node (ref "P1") (pin "56") (pinfunction "56_56") (pintype "passive"))
      (node (ref "P1") (pin "58") (pinfunction "58_58") (pintype "passive"))
      (node (ref "P1") (pin "6") (pinfunction "6_6") (pintype "passive"))
      (node (ref "P1") (pin "60") (pinfunction "60_60") (pintype "passive"))
      (node (ref "P1") (pin "8") (pinfunction "8_8") (pintype "passive"))
      (node (ref "P2") (pin "1") (pinfunction "1_1") (pintype "passive"))
      (node (ref "P2") (pin "11") (pinfunction "11_11") (pintype "passive"))
      (node (ref "P2") (pin "13") (pinfunction "13_13") (pintype "passive"))
      (node (ref "P2") (pin "15") (pinfunction "15_15") (pintype "passive"))
      (node (ref "P2") (pin "17") (pinfunction "17_17") (pintype "passive"))
      (node (ref "P2") (pin "19") (pinfunction "19_19") (pintype "passive"))
      (node (ref "P2") (pin "21") (pinfunction "21_21") (pintype "passive"))
      (node (ref "P2") (pin "23") (pinfunction "23_23") (pintype "passive"))
      (node (ref "P2") (pin "25") (pinfunction "25_25") (pintype "passive"))
      (node (ref "P2") (pin "27") (pinfunction "27_27") (pintype "passive"))
      (node (ref "P2") (pin "29") (pinfunction "29_29") (pintype "passive"))
      (node (ref "P2") (pin "3") (pinfunction "3_3") (pintype "passive"))
      (node (ref "P2") (pin "31") (pinfunction "31_31") (pintype "passive"))
      (node (ref "P2") (pin "33") (pinfunction "33_33") (pintype "passive"))
      (node (ref "P2") (pin "35") (pinfunction "35_35") (pintype "passive"))
      (node (ref "P2") (pin "37") (pinfunction "37_37") (pintype "passive"))
      (node (ref "P2") (pin "39") (pinfunction "39_39") (pintype "passive"))
      (node (ref "P2") (pin "41") (pinfunction "41_41") (pintype "passive"))
      (node (ref "P2") (pin "43") (pinfunction "43_43") (pintype "passive"))
      (node (ref "P2") (pin "45") (pinfunction "45_45") (pintype "passive"))
      (node (ref "P2") (pin "47") (pinfunction "47_47") (pintype "passive"))
      (node (ref "P2") (pin "49") (pinfunction "49_49") (pintype "passive"))
      (node (ref "P2") (pin "5") (pinfunction "5_5") (pintype "passive"))
      (node (ref "P2") (pin "51") (pinfunction "51_51") (pintype "passive"))
      (node (ref "P2") (pin "53") (pinfunction "53_53") (pintype "passive"))
      (node (ref "P2") (pin "55") (pinfunction "55_55") (pintype "passive"))
      (node (ref "P2") (pin "57") (pinfunction "57_57") (pintype "passive"))
      (node (ref "P2") (pin "59") (pinfunction "59_59") (pintype "passive"))
      (node (ref "P2") (pin "7") (pinfunction "7_7") (pintype "passive"))
      (node (ref "P2") (pin "9") (pinfunction "9_9") (pintype "passive"))
      (node (ref "R1") (pin "2") (pinfunction "2_2") (pintype "passive"))
      (node (ref "R2") (pin "2") (pinfunction "2_2") (pintype "passive"))
      (node (ref "U1") (pin "1") (pinfunction "GND_1") (pintype "passive"))
      (node (ref "USB1") (pin "A12") (pinfunction "GND_A12") (pintype "passive"))
      (node (ref "USB1") (pin "B12") (pinfunction "GND_B12") (pintype "passive"))
    )
    (net (code "64") (name "Net-(F1-Pad2)") (class "Default")
      (node (ref "F1") (pin "2") (pinfunction "2_2") (pintype "passive"))
      (node (ref "S1") (pin "2") (pinfunction "2_2") (pintype "passive"))
      (node (ref "S1") (pin "5") (pinfunction "5_5") (pintype "passive"))
    )
    (net (code "65") (name "Net-(LED1-A)") (class "Default")
      (node (ref "LED1") (pin "1") (pinfunction "A_1") (pintype "passive"))
      (node (ref "R3") (pin "1") (pinfunction "1_1") (pintype "passive"))
    )
    (net (code "66") (name "Net-(USB1-CC1)") (class "Default")
      (node (ref "R2") (pin "1") (pinfunction "1_1") (pintype "passive"))
      (node (ref "USB1") (pin "A5") (pinfunction "CC1_A5") (pintype "passive"))
    )
    (net (code "67") (name "Net-(USB1-CC2)") (class "Default")
      (node (ref "R1") (pin "1") (pinfunction "1_1") (pintype "passive"))
      (node (ref "USB1") (pin "B5") (pinfunction "CC2_B5") (pintype "passive"))
    )
    (net (code "68") (name "VBUS") (class "Default")
      (node (ref "F1") (pin "1") (pinfunction "1_1") (pintype "passive"))
      (node (ref "USB1") (pin "A9") (pinfunction "VBus_A9") (pintype "passive"))
      (node (ref "USB1") (pin "B9") (pinfunction "VBus_B9") (pintype "passive"))
    )
    (net (code "69") (name "unconnected-(S1-Pad3)") (class "Default")
      (node (ref "S1") (pin "3") (pinfunction "3_3") (pintype "passive"))
    )
    (net (code "70") (name "unconnected-(S1-Pad6)") (class "Default")
      (node (ref "S1") (pin "6") (pinfunction "6_6") (pintype "passive"))
    )
    (net (code "71") (name "unconnected-(USB1-Pad1)") (class "Default")
      (node (ref "USB1") (pin "1") (pinfunction "1_1") (pintype "passive+no_connect"))
    )
    (net (code "72") (name "unconnected-(USB1-Pad2)") (class "Default")
      (node (ref "USB1") (pin "2") (pinfunction "2_2") (pintype "passive+no_connect"))
    )
    (net (code "73") (name "unconnected-(USB1-Pad3)") (class "Default")
      (node (ref "USB1") (pin "3") (pinfunction "3_3") (pintype "passive+no_connect"))
    )
    (net (code "74") (name "unconnected-(USB1-Pad4)") (class "Default")
      (node (ref "USB1") (pin "4") (pinfunction "4_4") (pintype "passive+no_connect"))
    )
  )
)
